# orao-keyboard-routed.net
KiCad netlist of a schematic drawn in EAGLE
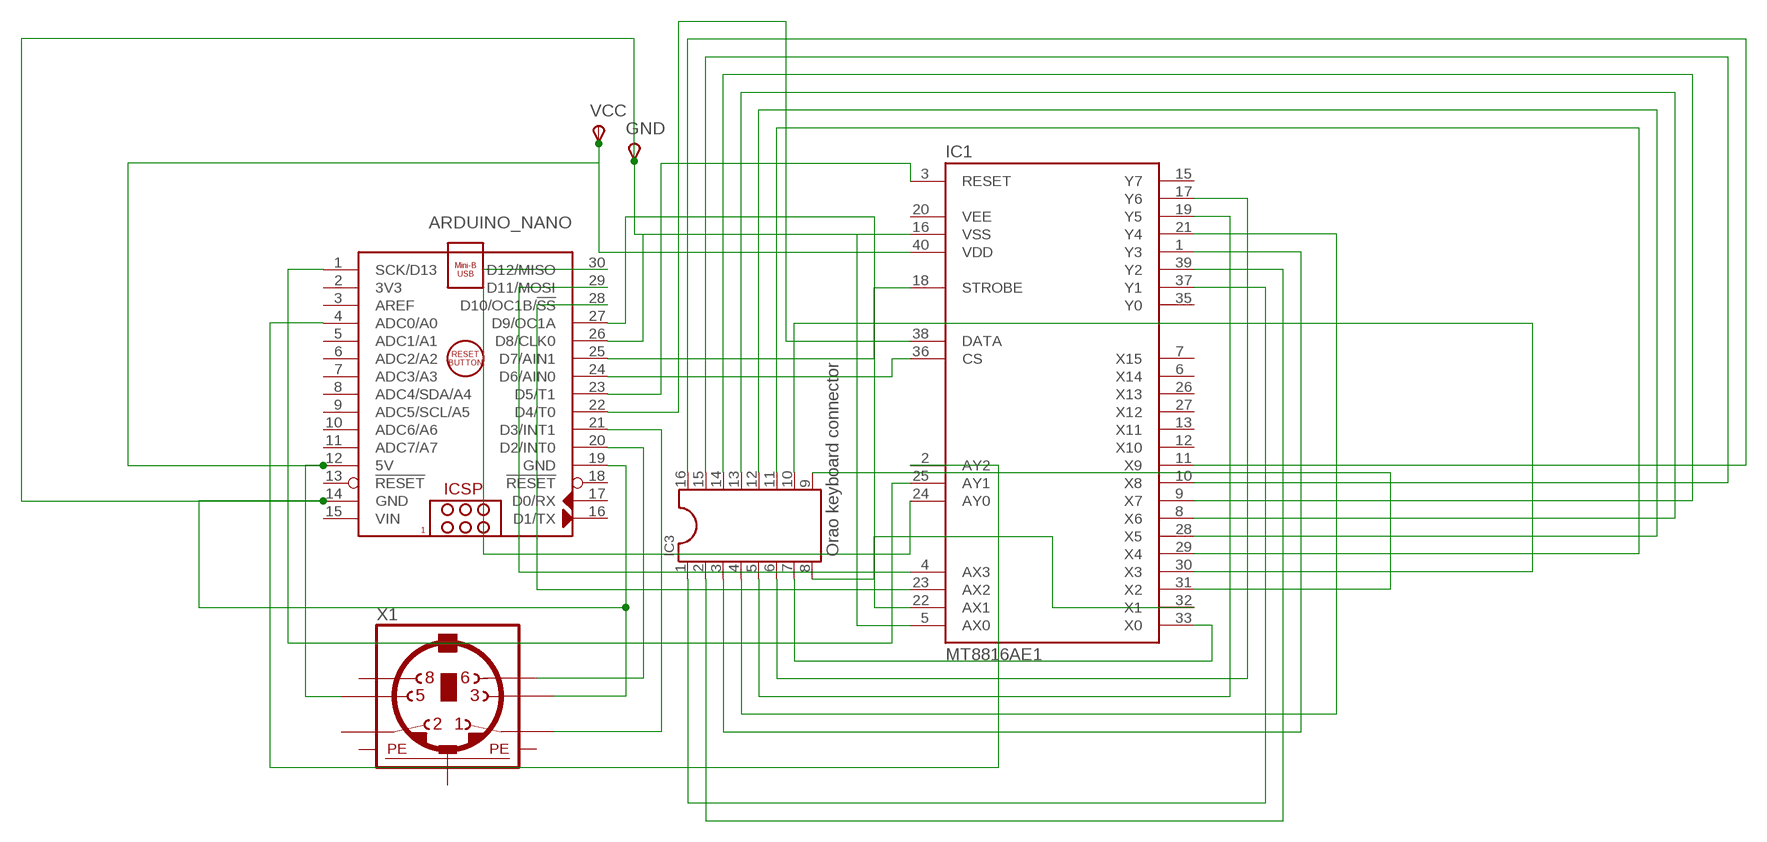
[diagram p0: schematic, sheet 1]

(export (version "E")
  (design (tool "Eeschema 10.0.6"))
  (components
    (comp (ref "ARDUINO_NANO")
      (value "ARDUINO_NANO")
      (footprint "eagle-import:ARDUINO_NANO")
      (libsource (lib "eagle-import") (part "ARDUINO_NANO"))
    )
    (comp (ref "GND")
      (value "TPSPAD1-13")
      (footprint "eagle-import:P1-13")
      (libsource (lib "eagle-import") (part "TPSPAD1-13"))
    )
    (comp (ref "IC1")
      (value "MT8816AE1")
      (footprint "eagle-import:DIL40")
      (libsource (lib "eagle-import") (part "MT8816AE1"))
    )
    (comp (ref "IC3")
      (value "Orao keyboard connector")
      (footprint "eagle-import:SOCKED-16")
      (libsource (lib "eagle-import") (part "DIL16S"))
    )
    (comp (ref "VCC")
      (value "TPSPAD1-13")
      (footprint "eagle-import:P1-13")
      (libsource (lib "eagle-import") (part "TPSPAD1-13"))
    )
    (comp (ref "X1")
      (value "MINI_DIN_6")
      (footprint "eagle-import:M_DIN6")
      (libsource (lib "eagle-import") (part "MINI_DIN_6"))
    )
  )
  (nets
    (net (code "1") (name "/PE1") (class "Default")
      (node (ref "X1") (pin "SH1") (pinfunction "PE1_SH1") (pintype "power_in"))
    )
    (net (code "2") (name "/PE2") (class "Default")
      (node (ref "X1") (pin "SH2") (pinfunction "PE2_SH2") (pintype "power_in"))
    )
    (net (code "3") (name "/PE3") (class "Default")
      (node (ref "X1") (pin "SH3") (pinfunction "PE3_SH3") (pintype "power_in"))
    )
    (net (code "4") (name "/VEE") (class "Default")
      (node (ref "IC1") (pin "20") (pinfunction "VEE_20") (pintype "power_in"))
    )
    (net (code "5") (name "/VIN") (class "Default")
      (node (ref "ARDUINO_NANO") (pin "15") (pinfunction "VIN_15") (pintype "power_in"))
    )
    (net (code "6") (name "Net-(ARDUINO_NANO-5V)") (class "Default")
      (node (ref "ARDUINO_NANO") (pin "12") (pinfunction "5V_12") (pintype "power_in"))
      (node (ref "IC1") (pin "40") (pinfunction "VDD_40") (pintype "power_in"))
      (node (ref "VCC") (pin "TP") (pinfunction "PP_TP") (pintype "input"))
      (node (ref "X1") (pin "5") (pinfunction "5_5") (pintype "passive"))
    )
    (net (code "7") (name "Net-(ARDUINO_NANO-ADC0{slash}A0)") (class "Default")
      (node (ref "ARDUINO_NANO") (pin "4") (pinfunction "ADC0/A0_4") (pintype "bidirectional"))
      (node (ref "IC1") (pin "2") (pinfunction "AY2_2") (pintype "input"))
    )
    (net (code "8") (name "Net-(ARDUINO_NANO-D2{slash}INT0)") (class "Default")
      (node (ref "ARDUINO_NANO") (pin "20") (pinfunction "D2/INT0_20") (pintype "bidirectional"))
      (node (ref "X1") (pin "6") (pinfunction "6_6") (pintype "passive"))
    )
    (net (code "9") (name "Net-(ARDUINO_NANO-D3{slash}INT1)") (class "Default")
      (node (ref "ARDUINO_NANO") (pin "21") (pinfunction "D3/INT1_21") (pintype "bidirectional"))
      (node (ref "X1") (pin "1") (pinfunction "1_1") (pintype "passive"))
    )
    (net (code "10") (name "Net-(ARDUINO_NANO-D4{slash}T0)") (class "Default")
      (node (ref "ARDUINO_NANO") (pin "22") (pinfunction "D4/T0_22") (pintype "bidirectional"))
      (node (ref "IC1") (pin "38") (pinfunction "DATA_38") (pintype "input"))
    )
    (net (code "11") (name "Net-(ARDUINO_NANO-D5{slash}T1)") (class "Default")
      (node (ref "ARDUINO_NANO") (pin "23") (pinfunction "D5/T1_23") (pintype "bidirectional"))
      (node (ref "IC1") (pin "3") (pinfunction "RESET_3") (pintype "input"))
    )
    (net (code "12") (name "Net-(ARDUINO_NANO-D6{slash}AIN0)") (class "Default")
      (node (ref "ARDUINO_NANO") (pin "24") (pinfunction "D6/AIN0_24") (pintype "bidirectional"))
      (node (ref "IC1") (pin "36") (pinfunction "CS_36") (pintype "input"))
    )
    (net (code "13") (name "Net-(ARDUINO_NANO-D7{slash}AIN1)") (class "Default")
      (node (ref "ARDUINO_NANO") (pin "25") (pinfunction "D7/AIN1_25") (pintype "bidirectional"))
      (node (ref "IC1") (pin "18") (pinfunction "STROBE_18") (pintype "input"))
    )
    (net (code "14") (name "Net-(ARDUINO_NANO-D8{slash}CLK0)") (class "Default")
      (node (ref "ARDUINO_NANO") (pin "26") (pinfunction "D8/CLK0_26") (pintype "bidirectional"))
      (node (ref "IC1") (pin "5") (pinfunction "AX0_5") (pintype "input"))
    )
    (net (code "15") (name "Net-(ARDUINO_NANO-D9{slash}OC1A)") (class "Default")
      (node (ref "ARDUINO_NANO") (pin "27") (pinfunction "D9/OC1A_27") (pintype "bidirectional"))
      (node (ref "IC1") (pin "22") (pinfunction "AX1_22") (pintype "input"))
    )
    (net (code "16") (name "Net-(ARDUINO_NANO-D10{slash}OC1B{slash}~{SS})") (class "Default")
      (node (ref "ARDUINO_NANO") (pin "28") (pinfunction "D10/OC1B/~{SS}_28") (pintype "bidirectional"))
      (node (ref "IC1") (pin "23") (pinfunction "AX2_23") (pintype "input"))
    )
    (net (code "17") (name "Net-(ARDUINO_NANO-D11{slash}MOSI)") (class "Default")
      (node (ref "ARDUINO_NANO") (pin "29") (pinfunction "D11/MOSI_29") (pintype "bidirectional"))
      (node (ref "IC1") (pin "4") (pinfunction "AX3_4") (pintype "input"))
    )
    (net (code "18") (name "Net-(ARDUINO_NANO-D12{slash}MISO)") (class "Default")
      (node (ref "ARDUINO_NANO") (pin "30") (pinfunction "D12/MISO_30") (pintype "bidirectional"))
      (node (ref "IC1") (pin "24") (pinfunction "AY0_24") (pintype "input"))
    )
    (net (code "19") (name "Net-(ARDUINO_NANO-SCK{slash}D13)") (class "Default")
      (node (ref "ARDUINO_NANO") (pin "1") (pinfunction "SCK/D13_1") (pintype "bidirectional"))
      (node (ref "IC1") (pin "25") (pinfunction "AY1_25") (pintype "input"))
    )
    (net (code "20") (name "Net-(GND-PP)") (class "Default")
      (node (ref "ARDUINO_NANO") (pin "14") (pinfunction "GND_14") (pintype "power_in"))
      (node (ref "ARDUINO_NANO") (pin "19") (pinfunction "GND_19") (pintype "power_in"))
      (node (ref "GND") (pin "TP") (pinfunction "PP_TP") (pintype "input"))
      (node (ref "IC1") (pin "16") (pinfunction "VSS_16") (pintype "power_in"))
      (node (ref "X1") (pin "3") (pinfunction "3_3") (pintype "passive"))
    )
    (net (code "21") (name "Net-(IC1-X0)") (class "Default")
      (node (ref "IC1") (pin "33") (pinfunction "X0_33") (pintype "bidirectional"))
      (node (ref "IC3") (pin "7") (pinfunction "7_7") (pintype "passive"))
    )
    (net (code "22") (name "Net-(IC1-X1)") (class "Default")
      (node (ref "IC1") (pin "32") (pinfunction "X1_32") (pintype "bidirectional"))
      (node (ref "IC3") (pin "8") (pinfunction "8_8") (pintype "passive"))
    )
    (net (code "23") (name "Net-(IC1-X2)") (class "Default")
      (node (ref "IC1") (pin "31") (pinfunction "X2_31") (pintype "bidirectional"))
      (node (ref "IC3") (pin "9") (pinfunction "9_9") (pintype "passive"))
    )
    (net (code "24") (name "Net-(IC1-X3)") (class "Default")
      (node (ref "IC1") (pin "30") (pinfunction "X3_30") (pintype "bidirectional"))
      (node (ref "IC3") (pin "10") (pinfunction "10_10") (pintype "passive"))
    )
    (net (code "25") (name "Net-(IC1-X4)") (class "Default")
      (node (ref "IC1") (pin "29") (pinfunction "X4_29") (pintype "bidirectional"))
      (node (ref "IC3") (pin "11") (pinfunction "11_11") (pintype "passive"))
    )
    (net (code "26") (name "Net-(IC1-X5)") (class "Default")
      (node (ref "IC1") (pin "28") (pinfunction "X5_28") (pintype "bidirectional"))
      (node (ref "IC3") (pin "12") (pinfunction "12_12") (pintype "passive"))
    )
    (net (code "27") (name "Net-(IC1-X6)") (class "Default")
      (node (ref "IC1") (pin "8") (pinfunction "X6_8") (pintype "bidirectional"))
      (node (ref "IC3") (pin "13") (pinfunction "13_13") (pintype "passive"))
    )
    (net (code "28") (name "Net-(IC1-X7)") (class "Default")
      (node (ref "IC1") (pin "9") (pinfunction "X7_9") (pintype "bidirectional"))
      (node (ref "IC3") (pin "14") (pinfunction "14_14") (pintype "passive"))
    )
    (net (code "29") (name "Net-(IC1-X8)") (class "Default")
      (node (ref "IC1") (pin "10") (pinfunction "X8_10") (pintype "bidirectional"))
      (node (ref "IC3") (pin "15") (pinfunction "15_15") (pintype "passive"))
    )
    (net (code "30") (name "Net-(IC1-X9)") (class "Default")
      (node (ref "IC1") (pin "11") (pinfunction "X9_11") (pintype "bidirectional"))
      (node (ref "IC3") (pin "16") (pinfunction "16_16") (pintype "passive"))
    )
    (net (code "31") (name "Net-(IC1-Y1)") (class "Default")
      (node (ref "IC1") (pin "37") (pinfunction "Y1_37") (pintype "bidirectional"))
      (node (ref "IC3") (pin "1") (pinfunction "1_1") (pintype "passive"))
    )
    (net (code "32") (name "Net-(IC1-Y2)") (class "Default")
      (node (ref "IC1") (pin "39") (pinfunction "Y2_39") (pintype "bidirectional"))
      (node (ref "IC3") (pin "2") (pinfunction "2_2") (pintype "passive"))
    )
    (net (code "33") (name "Net-(IC1-Y3)") (class "Default")
      (node (ref "IC1") (pin "1") (pinfunction "Y3_1") (pintype "bidirectional"))
      (node (ref "IC3") (pin "3") (pinfunction "3_3") (pintype "passive"))
    )
    (net (code "34") (name "Net-(IC1-Y4)") (class "Default")
      (node (ref "IC1") (pin "21") (pinfunction "Y4_21") (pintype "bidirectional"))
      (node (ref "IC3") (pin "4") (pinfunction "4_4") (pintype "passive"))
    )
    (net (code "35") (name "Net-(IC1-Y5)") (class "Default")
      (node (ref "IC1") (pin "19") (pinfunction "Y5_19") (pintype "bidirectional"))
      (node (ref "IC3") (pin "5") (pinfunction "5_5") (pintype "passive"))
    )
    (net (code "36") (name "Net-(IC1-Y6)") (class "Default")
      (node (ref "IC1") (pin "17") (pinfunction "Y6_17") (pintype "bidirectional"))
      (node (ref "IC3") (pin "6") (pinfunction "6_6") (pintype "passive"))
    )
    (net (code "37") (name "unconnected-(ARDUINO_NANO-3V3-Pad2)") (class "Default")
      (node (ref "ARDUINO_NANO") (pin "2") (pinfunction "3V3_2") (pintype "output"))
    )
    (net (code "38") (name "unconnected-(ARDUINO_NANO-ADC1{slash}A1-Pad5)") (class "Default")
      (node (ref "ARDUINO_NANO") (pin "5") (pinfunction "ADC1/A1_5") (pintype "bidirectional"))
    )
    (net (code "39") (name "unconnected-(ARDUINO_NANO-ADC2{slash}A2-Pad6)") (class "Default")
      (node (ref "ARDUINO_NANO") (pin "6") (pinfunction "ADC2/A2_6") (pintype "bidirectional"))
    )
    (net (code "40") (name "unconnected-(ARDUINO_NANO-ADC3{slash}A3-Pad7)") (class "Default")
      (node (ref "ARDUINO_NANO") (pin "7") (pinfunction "ADC3/A3_7") (pintype "bidirectional"))
    )
    (net (code "41") (name "unconnected-(ARDUINO_NANO-ADC4{slash}SDA{slash}A4-Pad8)") (class "Default")
      (node (ref "ARDUINO_NANO") (pin "8") (pinfunction "ADC4/SDA/A4_8") (pintype "bidirectional"))
    )
    (net (code "42") (name "unconnected-(ARDUINO_NANO-ADC5{slash}SCL{slash}A5-Pad9)") (class "Default")
      (node (ref "ARDUINO_NANO") (pin "9") (pinfunction "ADC5/SCL/A5_9") (pintype "bidirectional"))
    )
    (net (code "43") (name "unconnected-(ARDUINO_NANO-ADC6{slash}A6-Pad10)") (class "Default")
      (node (ref "ARDUINO_NANO") (pin "10") (pinfunction "ADC6/A6_10") (pintype "bidirectional"))
    )
    (net (code "44") (name "unconnected-(ARDUINO_NANO-ADC7{slash}A7-Pad11)") (class "Default")
      (node (ref "ARDUINO_NANO") (pin "11") (pinfunction "ADC7/A7_11") (pintype "bidirectional"))
    )
    (net (code "45") (name "unconnected-(ARDUINO_NANO-AREF-Pad3)") (class "Default")
      (node (ref "ARDUINO_NANO") (pin "3") (pinfunction "AREF_3") (pintype "input"))
    )
    (net (code "46") (name "unconnected-(ARDUINO_NANO-D0{slash}RX-Pad17)") (class "Default")
      (node (ref "ARDUINO_NANO") (pin "17") (pinfunction "D0/RX_17") (pintype "bidirectional"))
    )
    (net (code "47") (name "unconnected-(ARDUINO_NANO-D1{slash}TX-Pad16)") (class "Default")
      (node (ref "ARDUINO_NANO") (pin "16") (pinfunction "D1/TX_16") (pintype "bidirectional"))
    )
    (net (code "48") (name "unconnected-(ARDUINO_NANO-~{RESET}-Pad13)") (class "Default")
      (node (ref "ARDUINO_NANO") (pin "13") (pinfunction "~{RESET}_13") (pintype "input"))
    )
    (net (code "49") (name "unconnected-(ARDUINO_NANO-~{RESET}-Pad18)") (class "Default")
      (node (ref "ARDUINO_NANO") (pin "18") (pinfunction "~{RESET}_18") (pintype "input"))
    )
    (net (code "50") (name "unconnected-(IC1-X10-Pad12)") (class "Default")
      (node (ref "IC1") (pin "12") (pinfunction "X10_12") (pintype "bidirectional"))
    )
    (net (code "51") (name "unconnected-(IC1-X11-Pad13)") (class "Default")
      (node (ref "IC1") (pin "13") (pinfunction "X11_13") (pintype "bidirectional"))
    )
    (net (code "52") (name "unconnected-(IC1-X12-Pad27)") (class "Default")
      (node (ref "IC1") (pin "27") (pinfunction "X12_27") (pintype "bidirectional"))
    )
    (net (code "53") (name "unconnected-(IC1-X13-Pad26)") (class "Default")
      (node (ref "IC1") (pin "26") (pinfunction "X13_26") (pintype "bidirectional"))
    )
    (net (code "54") (name "unconnected-(IC1-X14-Pad6)") (class "Default")
      (node (ref "IC1") (pin "6") (pinfunction "X14_6") (pintype "bidirectional"))
    )
    (net (code "55") (name "unconnected-(IC1-X15-Pad7)") (class "Default")
      (node (ref "IC1") (pin "7") (pinfunction "X15_7") (pintype "bidirectional"))
    )
    (net (code "56") (name "unconnected-(IC1-Y0-Pad35)") (class "Default")
      (node (ref "IC1") (pin "35") (pinfunction "Y0_35") (pintype "bidirectional"))
    )
    (net (code "57") (name "unconnected-(IC1-Y7-Pad15)") (class "Default")
      (node (ref "IC1") (pin "15") (pinfunction "Y7_15") (pintype "bidirectional"))
    )
    (net (code "58") (name "unconnected-(X1-Pad2)") (class "Default")
      (node (ref "X1") (pin "2") (pinfunction "2_2") (pintype "passive"))
    )
    (net (code "59") (name "unconnected-(X1-Pad8)") (class "Default")
      (node (ref "X1") (pin "8") (pinfunction "8_8") (pintype "passive"))
    )
  )
)
